# PI_R3_REV1_BUTTONS.net
KiCad netlist of a schematic drawn in Altium Designer
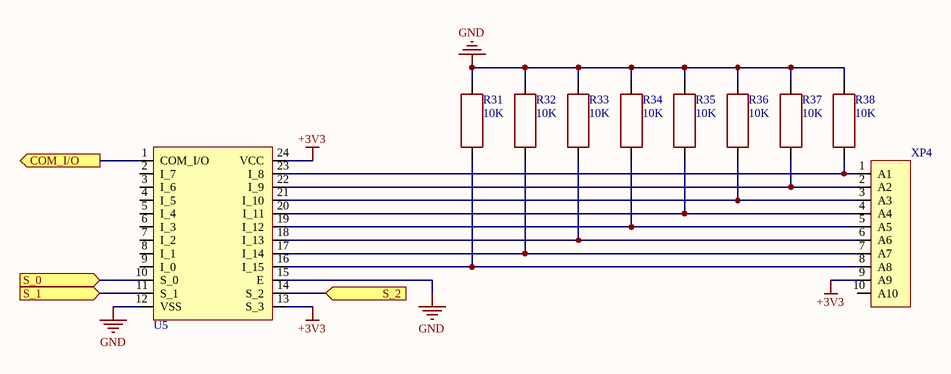
[diagram p0: PI_R3_REV1_BUTTONS.SchDoc]

(export (version "E")
  (design (tool "Eeschema 10.0.6"))
  (components
    (comp (ref "R31")
      (value "10K")
      (footprint "RES: 0402")
      (fields (field (name "TOLERANCE") "±5%"))
      (libsource (lib "resistor") (part "Resistor_0402"))
    )
    (comp (ref "R32")
      (value "10K")
      (footprint "RES: 0402")
      (fields (field (name "TOLERANCE") "±5%"))
      (libsource (lib "resistor") (part "Resistor_0402"))
    )
    (comp (ref "R33")
      (value "10K")
      (footprint "RES: 0402")
      (fields (field (name "TOLERANCE") "±5%"))
      (libsource (lib "resistor") (part "Resistor_0402"))
    )
    (comp (ref "R34")
      (value "10K")
      (footprint "RES: 0402")
      (fields (field (name "TOLERANCE") "±5%"))
      (libsource (lib "resistor") (part "Resistor_0402"))
    )
    (comp (ref "R35")
      (value "10K")
      (footprint "RES: 0402")
      (fields (field (name "TOLERANCE") "±5%"))
      (libsource (lib "resistor") (part "Resistor_0402"))
    )
    (comp (ref "R36")
      (value "10K")
      (footprint "RES: 0402")
      (fields (field (name "TOLERANCE") "±5%"))
      (libsource (lib "resistor") (part "Resistor_0402"))
    )
    (comp (ref "R37")
      (value "10K")
      (footprint "RES: 0402")
      (fields (field (name "TOLERANCE") "±5%"))
      (libsource (lib "resistor") (part "Resistor_0402"))
    )
    (comp (ref "R38")
      (value "10K")
      (footprint "RES: 0402")
      (fields (field (name "TOLERANCE") "±5%"))
      (libsource (lib "resistor") (part "Resistor_0402"))
    )
    (comp (ref "U5")
      (value "CD74HC4067M96")
      (footprint "SOIC-24")
      (description "1 MHz, Low-Power Op Amp")
      (fields (field (name "MANUFACTURER") "Texas Instruments"))
      (libsource (lib "MY_INT_LIB") (part "CD74HC4067M96"))
    )
    (comp (ref "XP4")
      (value "10FDZ-BT")
      (footprint "10FDZ-BT")
      (fields (field (name "MANUFACTURER") "JST"))
      (libsource (lib "MY_INT_LIB") (part "10FDZ-BT"))
    )
  )
  (nets
    (net (code "1") (name "+3V3") (class "Default")
      (node (ref "U5") (pin "13") (pinfunction "S_3_13") (pintype "passive"))
      (node (ref "U5") (pin "24") (pinfunction "VCC_24") (pintype "power_in"))
      (node (ref "XP4") (pin "9") (pinfunction "A9_9") (pintype "passive"))
    )
    (net (code "2") (name "/COM_I{slash}O") (class "Default")
      (node (ref "U5") (pin "1") (pinfunction "COM_I/O_1") (pintype "passive"))
    )
    (net (code "3") (name "/S_0") (class "Default")
      (node (ref "U5") (pin "10") (pinfunction "S_0_10") (pintype "passive"))
    )
    (net (code "4") (name "/S_1") (class "Default")
      (node (ref "U5") (pin "11") (pinfunction "S_1_11") (pintype "passive"))
    )
    (net (code "5") (name "/S_2") (class "Default")
      (node (ref "U5") (pin "14") (pinfunction "S_2_14") (pintype "passive"))
    )
    (net (code "6") (name "GND") (class "Default")
      (node (ref "R31") (pin "1") (pinfunction "1_1") (pintype "passive"))
      (node (ref "R32") (pin "1") (pinfunction "1_1") (pintype "passive"))
      (node (ref "R33") (pin "1") (pinfunction "1_1") (pintype "passive"))
      (node (ref "R34") (pin "1") (pinfunction "1_1") (pintype "passive"))
      (node (ref "R35") (pin "1") (pinfunction "1_1") (pintype "passive"))
      (node (ref "R36") (pin "1") (pinfunction "1_1") (pintype "passive"))
      (node (ref "R37") (pin "1") (pinfunction "1_1") (pintype "passive"))
      (node (ref "R38") (pin "1") (pinfunction "1_1") (pintype "passive"))
      (node (ref "U5") (pin "12") (pinfunction "VSS_12") (pintype "power_in"))
      (node (ref "U5") (pin "15") (pinfunction "E_15") (pintype "passive"))
    )
    (net (code "7") (name "Net-(U5-I_8)") (class "Default")
      (node (ref "R38") (pin "2") (pinfunction "2_2") (pintype "passive"))
      (node (ref "U5") (pin "23") (pinfunction "I_8_23") (pintype "passive"))
      (node (ref "XP4") (pin "1") (pinfunction "A1_1") (pintype "passive"))
    )
    (net (code "8") (name "Net-(U5-I_9)") (class "Default")
      (node (ref "R37") (pin "2") (pinfunction "2_2") (pintype "passive"))
      (node (ref "U5") (pin "22") (pinfunction "I_9_22") (pintype "passive"))
      (node (ref "XP4") (pin "2") (pinfunction "A2_2") (pintype "passive"))
    )
    (net (code "9") (name "Net-(U5-I_10)") (class "Default")
      (node (ref "R36") (pin "2") (pinfunction "2_2") (pintype "passive"))
      (node (ref "U5") (pin "21") (pinfunction "I_10_21") (pintype "passive"))
      (node (ref "XP4") (pin "3") (pinfunction "A3_3") (pintype "passive"))
    )
    (net (code "10") (name "Net-(U5-I_11)") (class "Default")
      (node (ref "R35") (pin "2") (pinfunction "2_2") (pintype "passive"))
      (node (ref "U5") (pin "20") (pinfunction "I_11_20") (pintype "passive"))
      (node (ref "XP4") (pin "4") (pinfunction "A4_4") (pintype "passive"))
    )
    (net (code "11") (name "Net-(U5-I_12)") (class "Default")
      (node (ref "R34") (pin "2") (pinfunction "2_2") (pintype "passive"))
      (node (ref "U5") (pin "19") (pinfunction "I_12_19") (pintype "passive"))
      (node (ref "XP4") (pin "5") (pinfunction "A5_5") (pintype "passive"))
    )
    (net (code "12") (name "Net-(U5-I_13)") (class "Default")
      (node (ref "R33") (pin "2") (pinfunction "2_2") (pintype "passive"))
      (node (ref "U5") (pin "18") (pinfunction "I_13_18") (pintype "passive"))
      (node (ref "XP4") (pin "6") (pinfunction "A6_6") (pintype "passive"))
    )
    (net (code "13") (name "Net-(U5-I_14)") (class "Default")
      (node (ref "R32") (pin "2") (pinfunction "2_2") (pintype "passive"))
      (node (ref "U5") (pin "17") (pinfunction "I_14_17") (pintype "passive"))
      (node (ref "XP4") (pin "7") (pinfunction "A7_7") (pintype "passive"))
    )
    (net (code "14") (name "Net-(U5-I_15)") (class "Default")
      (node (ref "R31") (pin "2") (pinfunction "2_2") (pintype "passive"))
      (node (ref "U5") (pin "16") (pinfunction "I_15_16") (pintype "passive"))
      (node (ref "XP4") (pin "8") (pinfunction "A8_8") (pintype "passive"))
    )
    (net (code "15") (name "unconnected-(U5-I_0-Pad9)") (class "Default")
      (node (ref "U5") (pin "9") (pinfunction "I_0_9") (pintype "passive"))
    )
    (net (code "16") (name "unconnected-(U5-I_1-Pad8)") (class "Default")
      (node (ref "U5") (pin "8") (pinfunction "I_1_8") (pintype "passive"))
    )
    (net (code "17") (name "unconnected-(U5-I_2-Pad7)") (class "Default")
      (node (ref "U5") (pin "7") (pinfunction "I_2_7") (pintype "passive"))
    )
    (net (code "18") (name "unconnected-(U5-I_3-Pad6)") (class "Default")
      (node (ref "U5") (pin "6") (pinfunction "I_3_6") (pintype "passive"))
    )
    (net (code "19") (name "unconnected-(U5-I_4-Pad5)") (class "Default")
      (node (ref "U5") (pin "5") (pinfunction "I_4_5") (pintype "passive"))
    )
    (net (code "20") (name "unconnected-(U5-I_5-Pad4)") (class "Default")
      (node (ref "U5") (pin "4") (pinfunction "I_5_4") (pintype "passive"))
    )
    (net (code "21") (name "unconnected-(U5-I_6-Pad3)") (class "Default")
      (node (ref "U5") (pin "3") (pinfunction "I_6_3") (pintype "passive"))
    )
    (net (code "22") (name "unconnected-(U5-I_7-Pad2)") (class "Default")
      (node (ref "U5") (pin "2") (pinfunction "I_7_2") (pintype "passive"))
    )
    (net (code "23") (name "unconnected-(XP4-A10-Pad10)") (class "Default")
      (node (ref "XP4") (pin "10") (pinfunction "A10_10") (pintype "passive"))
    )
  )
)
